# rc-light-controller-tlc5940-smd.net
KiCad netlist of a schematic drawn in EAGLE
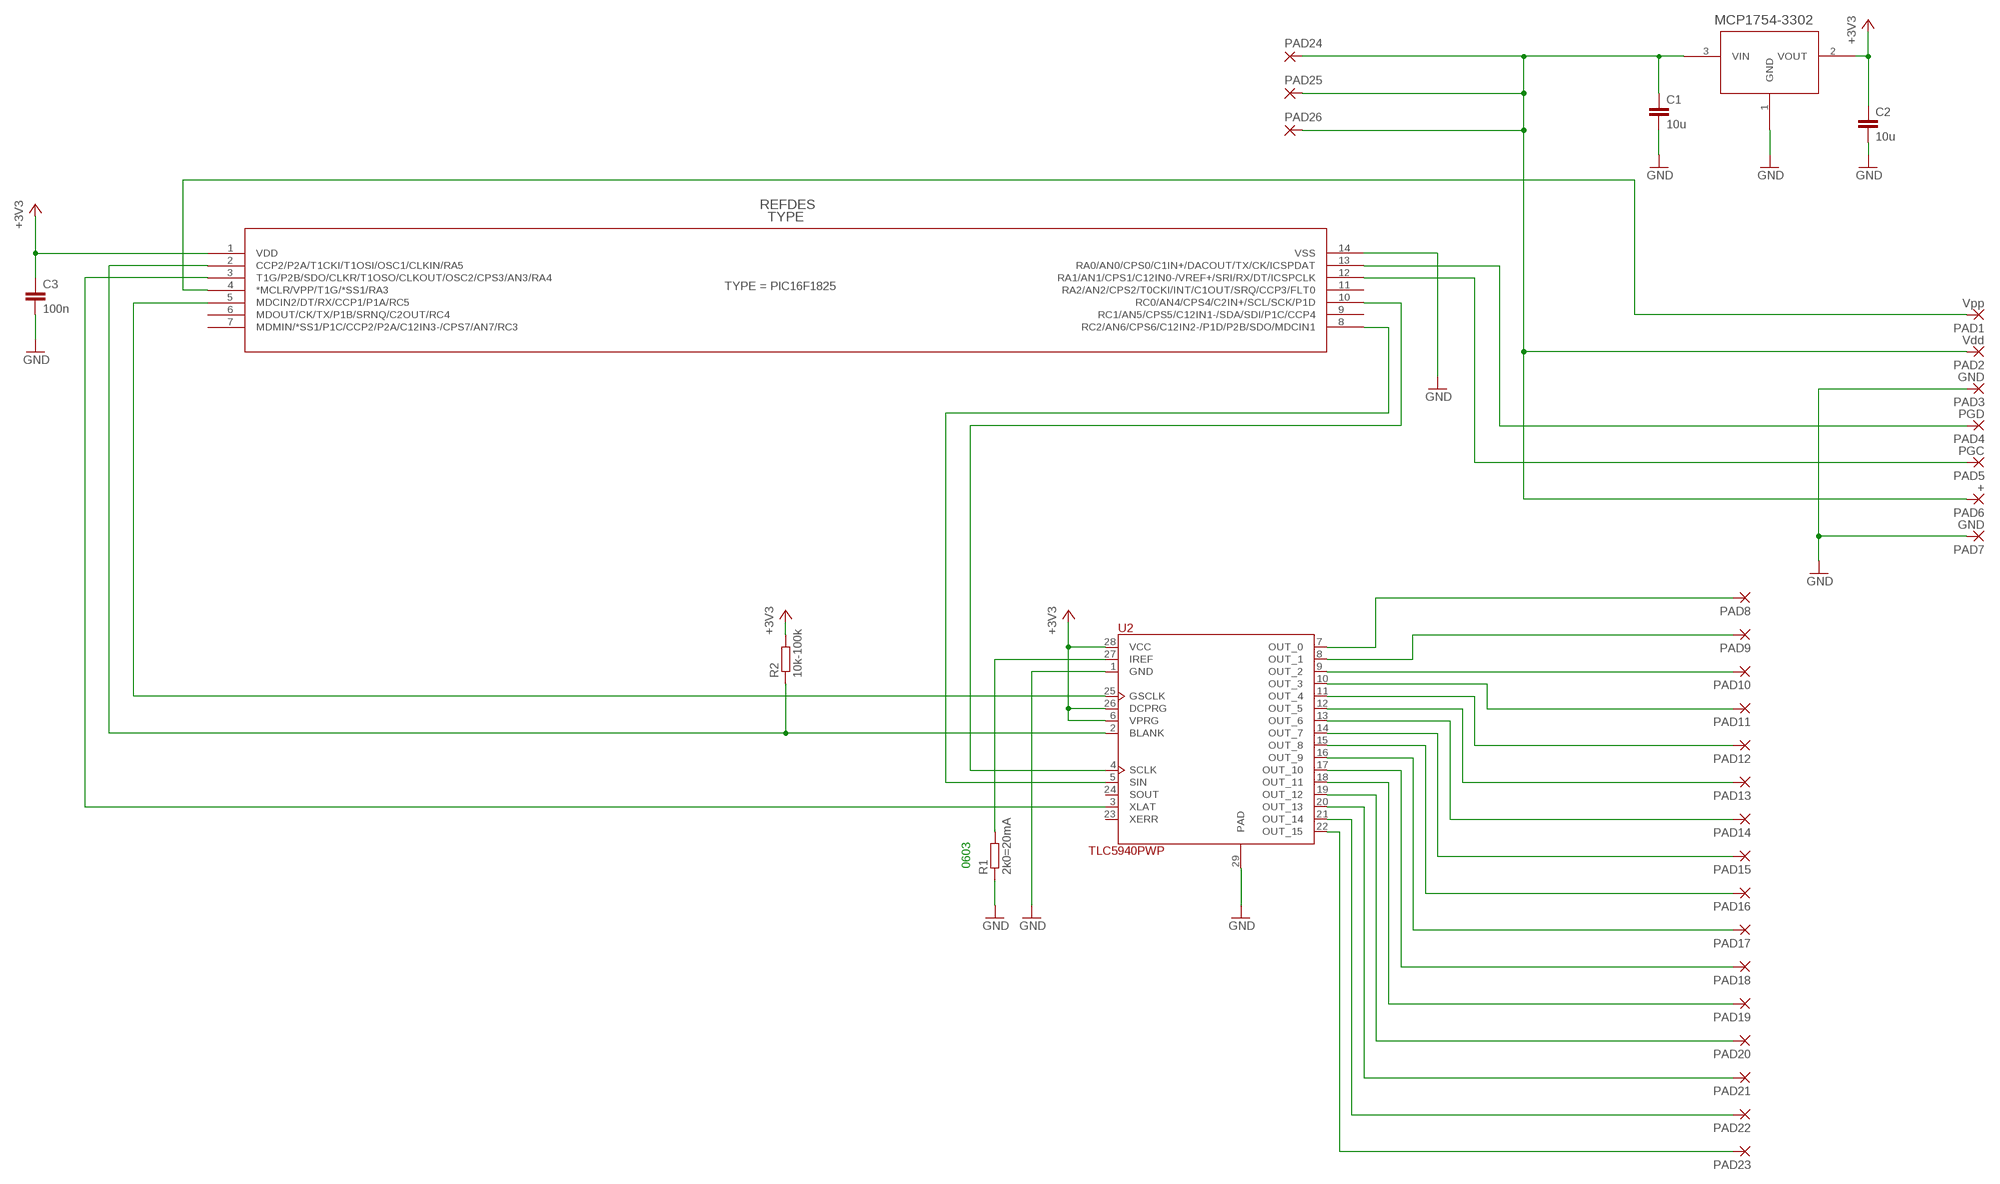
[diagram p0: schematic, sheet 1, part 1 of 2]
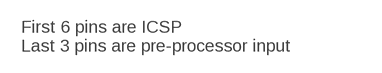
[diagram p1: schematic, sheet 1, part 2 of 2]

(export (version "E")
  (design (tool "Eeschema 10.0.6"))
  (components
    (comp (ref "C1")
      (value "10u")
      (footprint "eagle-import:C0805")
      (libsource (lib "eagle-import") (part "C-EUC0805"))
    )
    (comp (ref "C2")
      (value "10u")
      (footprint "eagle-import:C0805")
      (libsource (lib "eagle-import") (part "C-EUC0805"))
    )
    (comp (ref "C3")
      (value "100n")
      (footprint "eagle-import:C0805")
      (libsource (lib "eagle-import") (part "C-EUC0805"))
    )
    (comp (ref "PAD1")
      (value "Vpp")
      (footprint "eagle-import:SMD80X120")
      (libsource (lib "eagle-import") (part "SDM80X120"))
    )
    (comp (ref "PAD2")
      (value "Vdd")
      (footprint "eagle-import:SMD80X120")
      (libsource (lib "eagle-import") (part "SDM80X120"))
    )
    (comp (ref "PAD3")
      (value "GND")
      (footprint "eagle-import:SMD80X120")
      (libsource (lib "eagle-import") (part "SDM80X120"))
    )
    (comp (ref "PAD4")
      (value "PGD")
      (footprint "eagle-import:SMD80X120")
      (libsource (lib "eagle-import") (part "SDM80X120"))
    )
    (comp (ref "PAD5")
      (value "PGC")
      (footprint "eagle-import:SMD80X120")
      (libsource (lib "eagle-import") (part "SDM80X120"))
    )
    (comp (ref "PAD6")
      (value "+")
      (footprint "eagle-import:SMD80X120")
      (libsource (lib "eagle-import") (part "SDM80X120"))
    )
    (comp (ref "PAD7")
      (value "GND")
      (footprint "eagle-import:SMD80X120")
      (libsource (lib "eagle-import") (part "SDM80X120"))
    )
    (comp (ref "PAD8")
      (value "SMD50X100")
      (footprint "eagle-import:SMD50X100")
      (libsource (lib "eagle-import") (part "SMD50X100"))
    )
    (comp (ref "PAD9")
      (value "SMD50X100")
      (footprint "eagle-import:SMD50X100")
      (libsource (lib "eagle-import") (part "SMD50X100"))
    )
    (comp (ref "PAD10")
      (value "SMD50X100")
      (footprint "eagle-import:SMD50X100")
      (libsource (lib "eagle-import") (part "SMD50X100"))
    )
    (comp (ref "PAD11")
      (value "SMD50X100")
      (footprint "eagle-import:SMD50X100")
      (libsource (lib "eagle-import") (part "SMD50X100"))
    )
    (comp (ref "PAD12")
      (value "SMD50X100")
      (footprint "eagle-import:SMD50X100")
      (libsource (lib "eagle-import") (part "SMD50X100"))
    )
    (comp (ref "PAD13")
      (value "SMD50X100")
      (footprint "eagle-import:SMD50X100")
      (libsource (lib "eagle-import") (part "SMD50X100"))
    )
    (comp (ref "PAD14")
      (value "SMD50X100")
      (footprint "eagle-import:SMD50X100")
      (libsource (lib "eagle-import") (part "SMD50X100"))
    )
    (comp (ref "PAD15")
      (value "SMD50X100")
      (footprint "eagle-import:SMD50X100")
      (libsource (lib "eagle-import") (part "SMD50X100"))
    )
    (comp (ref "PAD16")
      (value "SMD50X100")
      (footprint "eagle-import:SMD50X100")
      (libsource (lib "eagle-import") (part "SMD50X100"))
    )
    (comp (ref "PAD17")
      (value "SMD50X100")
      (footprint "eagle-import:SMD50X100")
      (libsource (lib "eagle-import") (part "SMD50X100"))
    )
    (comp (ref "PAD18")
      (value "SMD50X100")
      (footprint "eagle-import:SMD50X100")
      (libsource (lib "eagle-import") (part "SMD50X100"))
    )
    (comp (ref "PAD19")
      (value "SMD50X100")
      (footprint "eagle-import:SMD50X100")
      (libsource (lib "eagle-import") (part "SMD50X100"))
    )
    (comp (ref "PAD20")
      (value "SMD50X100")
      (footprint "eagle-import:SMD50X100")
      (libsource (lib "eagle-import") (part "SMD50X100"))
    )
    (comp (ref "PAD21")
      (value "SMD50X100")
      (footprint "eagle-import:SMD50X100")
      (libsource (lib "eagle-import") (part "SMD50X100"))
    )
    (comp (ref "PAD22")
      (value "SMD50X100")
      (footprint "eagle-import:SMD50X100")
      (libsource (lib "eagle-import") (part "SMD50X100"))
    )
    (comp (ref "PAD23")
      (value "SMD50X100")
      (footprint "eagle-import:SMD50X100")
      (libsource (lib "eagle-import") (part "SMD50X100"))
    )
    (comp (ref "PAD24")
      (value "SMD50X100")
      (footprint "eagle-import:SMD50X100")
      (libsource (lib "eagle-import") (part "SMD50X100"))
    )
    (comp (ref "PAD25")
      (value "SMD50X100")
      (footprint "eagle-import:SMD50X100")
      (libsource (lib "eagle-import") (part "SMD50X100"))
    )
    (comp (ref "PAD26")
      (value "SMD50X100")
      (footprint "eagle-import:SMD50X100")
      (libsource (lib "eagle-import") (part "SMD50X100"))
    )
    (comp (ref "R1")
      (value "2k0=20mA")
      (footprint "eagle-import:R0805")
      (libsource (lib "eagle-import") (part "R-EU_R0805"))
    )
    (comp (ref "R2")
      (value "10k-100k")
      (footprint "eagle-import:R0805")
      (libsource (lib "eagle-import") (part "R-EU_R0805"))
    )
    (comp (ref "U$1")
      (value "MCP1754X-XXXXX/C")
      (footprint "eagle-import:SOT-23A_MC")
      (libsource (lib "eagle-import") (part "MCP1754X-XXXXX/C"))
    )
    (comp (ref "U1")
      (value "PIC16F1825-X_SL")
      (footprint "eagle-import:SOIC14-N_MC")
      (fields (field (name "TYPE") "PIC16F1825"))
      (libsource (lib "eagle-import") (part "PIC16F1825-X_SL"))
    )
    (comp (ref "U2")
      (value "TLC5940PWP")
      (footprint "eagle-import:SOP65P640X120-29N")
      (libsource (lib "eagle-import") (part "TLC5940PWP"))
    )
  )
  (nets
    (net (code "1") (name "+3V3") (class "Default")
      (node (ref "C2") (pin "1") (pinfunction "1_1") (pintype "passive"))
      (node (ref "C3") (pin "1") (pinfunction "1_1") (pintype "passive"))
      (node (ref "R2") (pin "2") (pinfunction "2_2") (pintype "passive"))
      (node (ref "U$1") (pin "2") (pinfunction "VOUT_2") (pintype "passive"))
      (node (ref "U1") (pin "1") (pinfunction "VDD_1") (pintype "passive"))
      (node (ref "U2") (pin "26") (pinfunction "DCPRG_26") (pintype "input"))
      (node (ref "U2") (pin "28") (pinfunction "VCC_28") (pintype "power_in"))
      (node (ref "U2") (pin "6") (pinfunction "VPRG_6") (pintype "input"))
    )
    (net (code "2") (name "GND") (class "Default")
      (node (ref "C1") (pin "2") (pinfunction "2_2") (pintype "passive"))
      (node (ref "C2") (pin "2") (pinfunction "2_2") (pintype "passive"))
      (node (ref "C3") (pin "2") (pinfunction "2_2") (pintype "passive"))
      (node (ref "PAD3") (pin "1") (pinfunction "P_1") (pintype "passive"))
      (node (ref "PAD7") (pin "1") (pinfunction "P_1") (pintype "passive"))
      (node (ref "R1") (pin "1") (pinfunction "1_1") (pintype "passive"))
      (node (ref "U$1") (pin "1") (pinfunction "GND_1") (pintype "passive"))
      (node (ref "U1") (pin "14") (pinfunction "VSS_14") (pintype "passive"))
      (node (ref "U2") (pin "1") (pinfunction "GND_1") (pintype "power_in"))
      (node (ref "U2") (pin "29") (pinfunction "PAD_29") (pintype "passive"))
    )
    (net (code "3") (name "Net-(PAD1-P)") (class "Default")
      (node (ref "PAD1") (pin "1") (pinfunction "P_1") (pintype "passive"))
      (node (ref "U1") (pin "4") (pinfunction "*MCLR/VPP/T1G/*SS1/RA3_4") (pintype "passive"))
    )
    (net (code "4") (name "Net-(PAD2-P)") (class "Default")
      (node (ref "C1") (pin "1") (pinfunction "1_1") (pintype "passive"))
      (node (ref "PAD2") (pin "1") (pinfunction "P_1") (pintype "passive"))
      (node (ref "PAD24") (pin "1") (pinfunction "P_1") (pintype "passive"))
      (node (ref "PAD25") (pin "1") (pinfunction "P_1") (pintype "passive"))
      (node (ref "PAD26") (pin "1") (pinfunction "P_1") (pintype "passive"))
      (node (ref "PAD6") (pin "1") (pinfunction "P_1") (pintype "passive"))
      (node (ref "U$1") (pin "3") (pinfunction "VIN_3") (pintype "passive"))
    )
    (net (code "5") (name "Net-(PAD4-P)") (class "Default")
      (node (ref "PAD4") (pin "1") (pinfunction "P_1") (pintype "passive"))
      (node (ref "U1") (pin "13") (pinfunction "RA0/AN0/CPS0/C1IN+/DACOUT/TX/CK/ICSPDAT_13") (pintype "passive"))
    )
    (net (code "6") (name "Net-(PAD5-P)") (class "Default")
      (node (ref "PAD5") (pin "1") (pinfunction "P_1") (pintype "passive"))
      (node (ref "U1") (pin "12") (pinfunction "RA1/AN1/CPS1/C12IN0-/VREF+/SRI/RX/DT/ICSPCLK_12") (pintype "passive"))
    )
    (net (code "7") (name "Net-(PAD8-P)") (class "Default")
      (node (ref "PAD8") (pin "1") (pinfunction "P_1") (pintype "passive"))
      (node (ref "U2") (pin "7") (pinfunction "OUT_0_7") (pintype "output"))
    )
    (net (code "8") (name "Net-(PAD9-P)") (class "Default")
      (node (ref "PAD9") (pin "1") (pinfunction "P_1") (pintype "passive"))
      (node (ref "U2") (pin "8") (pinfunction "OUT_1_8") (pintype "output"))
    )
    (net (code "9") (name "Net-(PAD10-P)") (class "Default")
      (node (ref "PAD10") (pin "1") (pinfunction "P_1") (pintype "passive"))
      (node (ref "U2") (pin "9") (pinfunction "OUT_2_9") (pintype "output"))
    )
    (net (code "10") (name "Net-(PAD11-P)") (class "Default")
      (node (ref "PAD11") (pin "1") (pinfunction "P_1") (pintype "passive"))
      (node (ref "U2") (pin "10") (pinfunction "OUT_3_10") (pintype "output"))
    )
    (net (code "11") (name "Net-(PAD12-P)") (class "Default")
      (node (ref "PAD12") (pin "1") (pinfunction "P_1") (pintype "passive"))
      (node (ref "U2") (pin "11") (pinfunction "OUT_4_11") (pintype "output"))
    )
    (net (code "12") (name "Net-(PAD13-P)") (class "Default")
      (node (ref "PAD13") (pin "1") (pinfunction "P_1") (pintype "passive"))
      (node (ref "U2") (pin "12") (pinfunction "OUT_5_12") (pintype "output"))
    )
    (net (code "13") (name "Net-(PAD14-P)") (class "Default")
      (node (ref "PAD14") (pin "1") (pinfunction "P_1") (pintype "passive"))
      (node (ref "U2") (pin "13") (pinfunction "OUT_6_13") (pintype "output"))
    )
    (net (code "14") (name "Net-(PAD15-P)") (class "Default")
      (node (ref "PAD15") (pin "1") (pinfunction "P_1") (pintype "passive"))
      (node (ref "U2") (pin "14") (pinfunction "OUT_7_14") (pintype "output"))
    )
    (net (code "15") (name "Net-(PAD16-P)") (class "Default")
      (node (ref "PAD16") (pin "1") (pinfunction "P_1") (pintype "passive"))
      (node (ref "U2") (pin "15") (pinfunction "OUT_8_15") (pintype "output"))
    )
    (net (code "16") (name "Net-(PAD17-P)") (class "Default")
      (node (ref "PAD17") (pin "1") (pinfunction "P_1") (pintype "passive"))
      (node (ref "U2") (pin "16") (pinfunction "OUT_9_16") (pintype "output"))
    )
    (net (code "17") (name "Net-(PAD18-P)") (class "Default")
      (node (ref "PAD18") (pin "1") (pinfunction "P_1") (pintype "passive"))
      (node (ref "U2") (pin "17") (pinfunction "OUT_10_17") (pintype "output"))
    )
    (net (code "18") (name "Net-(PAD19-P)") (class "Default")
      (node (ref "PAD19") (pin "1") (pinfunction "P_1") (pintype "passive"))
      (node (ref "U2") (pin "18") (pinfunction "OUT_11_18") (pintype "output"))
    )
    (net (code "19") (name "Net-(PAD20-P)") (class "Default")
      (node (ref "PAD20") (pin "1") (pinfunction "P_1") (pintype "passive"))
      (node (ref "U2") (pin "19") (pinfunction "OUT_12_19") (pintype "output"))
    )
    (net (code "20") (name "Net-(PAD21-P)") (class "Default")
      (node (ref "PAD21") (pin "1") (pinfunction "P_1") (pintype "passive"))
      (node (ref "U2") (pin "20") (pinfunction "OUT_13_20") (pintype "output"))
    )
    (net (code "21") (name "Net-(PAD22-P)") (class "Default")
      (node (ref "PAD22") (pin "1") (pinfunction "P_1") (pintype "passive"))
      (node (ref "U2") (pin "21") (pinfunction "OUT_14_21") (pintype "output"))
    )
    (net (code "22") (name "Net-(PAD23-P)") (class "Default")
      (node (ref "PAD23") (pin "1") (pinfunction "P_1") (pintype "passive"))
      (node (ref "U2") (pin "22") (pinfunction "OUT_15_22") (pintype "output"))
    )
    (net (code "23") (name "Net-(U1-CCP2{slash}P2A{slash}T1CKI{slash}T1OSI{slash}OSC1{slash}CLKIN{slash}RA5)") (class "Default")
      (node (ref "R2") (pin "1") (pinfunction "1_1") (pintype "passive"))
      (node (ref "U1") (pin "2") (pinfunction "CCP2/P2A/T1CKI/T1OSI/OSC1/CLKIN/RA5_2") (pintype "passive"))
      (node (ref "U2") (pin "2") (pinfunction "BLANK_2") (pintype "input"))
    )
    (net (code "24") (name "Net-(U1-MDCIN2{slash}DT{slash}RX{slash}CCP1{slash}P1A{slash}RC5)") (class "Default")
      (node (ref "U1") (pin "5") (pinfunction "MDCIN2/DT/RX/CCP1/P1A/RC5_5") (pintype "passive"))
      (node (ref "U2") (pin "25") (pinfunction "GSCLK_25") (pintype "input"))
    )
    (net (code "25") (name "Net-(U1-RC0{slash}AN4{slash}CPS4{slash}C2IN+{slash}SCL{slash}SCK{slash}P1D)") (class "Default")
      (node (ref "U1") (pin "10") (pinfunction "RC0/AN4/CPS4/C2IN+/SCL/SCK/P1D_10") (pintype "passive"))
      (node (ref "U2") (pin "4") (pinfunction "SCLK_4") (pintype "input"))
    )
    (net (code "26") (name "Net-(U1-RC2{slash}AN6{slash}CPS6{slash}C12IN2-{slash}P1D{slash}P2B{slash}SDO{slash}MDCIN1)") (class "Default")
      (node (ref "U1") (pin "8") (pinfunction "RC2/AN6/CPS6/C12IN2-/P1D/P2B/SDO/MDCIN1_8") (pintype "passive"))
      (node (ref "U2") (pin "5") (pinfunction "SIN_5") (pintype "input"))
    )
    (net (code "27") (name "Net-(U1-T1G{slash}P2B{slash}SDO{slash}CLKR{slash}T1OSO{slash}CLKOUT{slash}OSC2{slash}CPS3{slash}AN3{slash}RA4)") (class "Default")
      (node (ref "U1") (pin "3") (pinfunction "T1G/P2B/SDO/CLKR/T1OSO/CLKOUT/OSC2/CPS3/AN3/RA4_3") (pintype "passive"))
      (node (ref "U2") (pin "3") (pinfunction "XLAT_3") (pintype "input"))
    )
    (net (code "28") (name "Net-(U2-IREF)") (class "Default")
      (node (ref "R1") (pin "2") (pinfunction "2_2") (pintype "passive"))
      (node (ref "U2") (pin "27") (pinfunction "IREF_27") (pintype "power_in"))
    )
    (net (code "29") (name "unconnected-(U1-MDMIN{slash}*SS1{slash}P1C{slash}CCP2{slash}P2A{slash}C12IN3-{slash}CPS7{slash}AN7{slash}RC3-Pad7)") (class "Default")
      (node (ref "U1") (pin "7") (pinfunction "MDMIN/*SS1/P1C/CCP2/P2A/C12IN3-/CPS7/AN7/RC3_7") (pintype "passive"))
    )
    (net (code "30") (name "unconnected-(U1-MDOUT{slash}CK{slash}TX{slash}P1B{slash}SRNQ{slash}C2OUT{slash}RC4-Pad6)") (class "Default")
      (node (ref "U1") (pin "6") (pinfunction "MDOUT/CK/TX/P1B/SRNQ/C2OUT/RC4_6") (pintype "passive"))
    )
    (net (code "31") (name "unconnected-(U1-RA2{slash}AN2{slash}CPS2{slash}T0CKI{slash}INT{slash}C1OUT{slash}SRQ{slash}CCP3{slash}FLT0-Pad11)") (class "Default")
      (node (ref "U1") (pin "11") (pinfunction "RA2/AN2/CPS2/T0CKI/INT/C1OUT/SRQ/CCP3/FLT0_11") (pintype "passive"))
    )
    (net (code "32") (name "unconnected-(U1-RC1{slash}AN5{slash}CPS5{slash}C12IN1-{slash}SDA{slash}SDI{slash}P1C{slash}CCP4-Pad9)") (class "Default")
      (node (ref "U1") (pin "9") (pinfunction "RC1/AN5/CPS5/C12IN1-/SDA/SDI/P1C/CCP4_9") (pintype "passive"))
    )
    (net (code "33") (name "unconnected-(U2-SOUT-Pad24)") (class "Default")
      (node (ref "U2") (pin "24") (pinfunction "SOUT_24") (pintype "output"))
    )
    (net (code "34") (name "unconnected-(U2-XERR-Pad23)") (class "Default")
      (node (ref "U2") (pin "23") (pinfunction "XERR_23") (pintype "output"))
    )
  )
)
